# max636.net
KiCad netlist of a schematic drawn in EAGLE
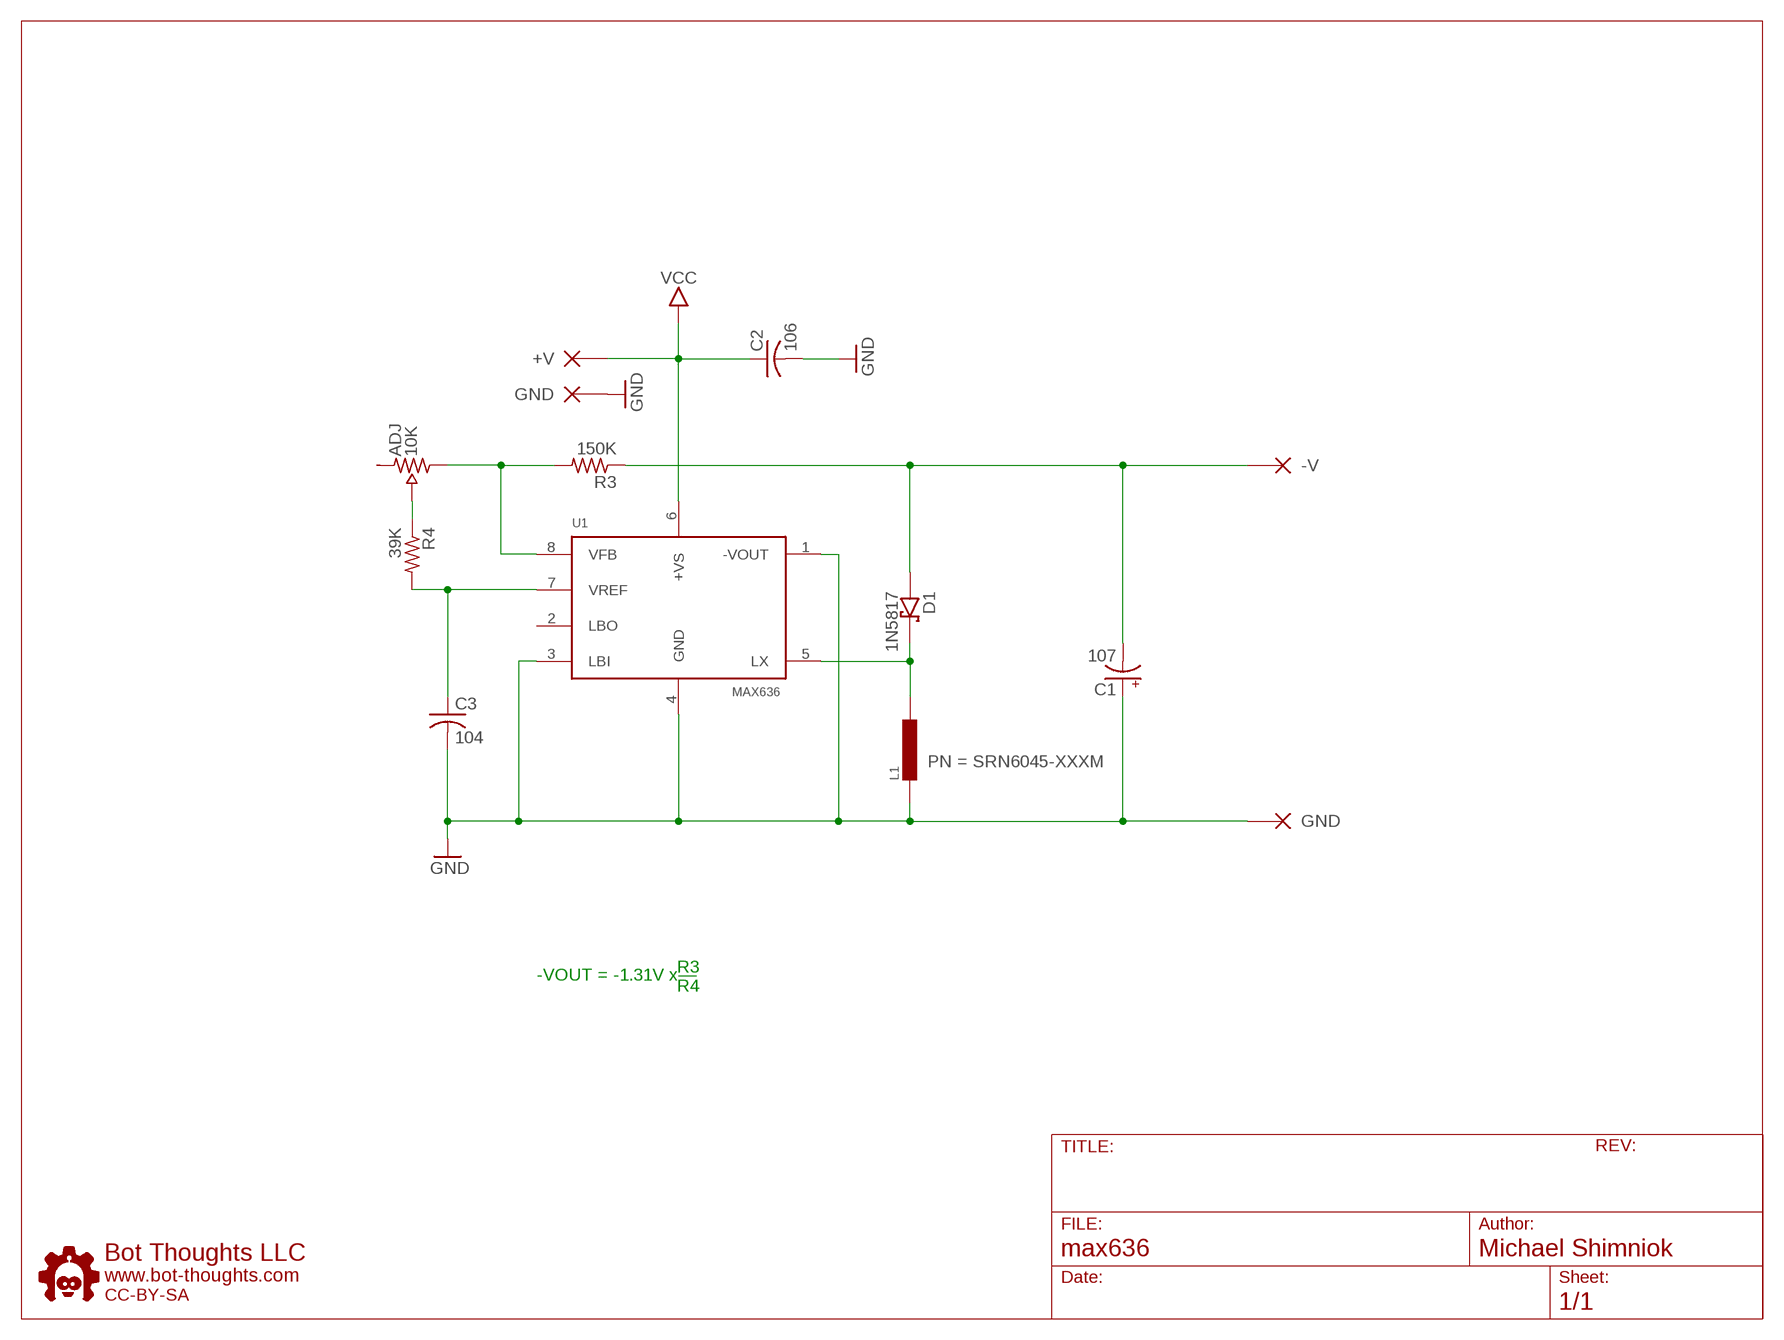
[diagram p0: schematic, sheet 1]

(export (version "E")
  (design (tool "Eeschema 10.0.6"))
  (components
    (comp (ref "ADJ")
      (value "10K")
      (footprint "eagle-import:35WR")
      (libsource (lib "eagle-import") (part "TRIM-35WR"))
    )
    (comp (ref "C1")
      (value "107")
      (footprint "eagle-import:SMC_B")
      (libsource (lib "eagle-import") (part "CPOL_SMC_B"))
    )
    (comp (ref "C2")
      (value "106")
      (footprint "eagle-import:0603")
      (libsource (lib "eagle-import") (part "C-0603"))
    )
    (comp (ref "C3")
      (value "104")
      (footprint "eagle-import:0603")
      (libsource (lib "eagle-import") (part "C-0603"))
    )
    (comp (ref "D1")
      (value "1N5817")
      (footprint "eagle-import:SOD-323")
      (libsource (lib "eagle-import") (part "SCHOTTKY-DIODE-B5817WS-TP"))
    )
    (comp (ref "J1")
      (value "+V")
      (footprint "eagle-import:1X01-S")
      (libsource (lib "eagle-import") (part "PINHEAD-1"))
    )
    (comp (ref "J2")
      (value "-V")
      (footprint "eagle-import:1X01-S")
      (libsource (lib "eagle-import") (part "PINHEAD-1"))
    )
    (comp (ref "J3")
      (value "GND")
      (footprint "eagle-import:1X01-S")
      (libsource (lib "eagle-import") (part "PINHEAD-1"))
    )
    (comp (ref "J4")
      (value "GND")
      (footprint "eagle-import:1X01-S")
      (libsource (lib "eagle-import") (part "PINHEAD-1"))
    )
    (comp (ref "L1")
      (value "INDUCTOR-VLS6045EX")
      (footprint "eagle-import:VLS6045EX")
      (fields (field (name "PN") "SRN6045-XXXM"))
      (libsource (lib "eagle-import") (part "INDUCTOR-VLS6045EX"))
    )
    (comp (ref "R3")
      (value "150K")
      (footprint "eagle-import:0603")
      (libsource (lib "eagle-import") (part "R0603"))
    )
    (comp (ref "R4")
      (value "39K")
      (footprint "eagle-import:0603")
      (libsource (lib "eagle-import") (part "R0603"))
    )
    (comp (ref "U$1")
      (value "BTLOGO-LOGO-SM")
      (footprint "eagle-import:BTLOGOS")
      (libsource (lib "eagle-import") (part "BTLOGO-LOGO-SM"))
    )
    (comp (ref "U1")
      (value "MAX636")
      (footprint "eagle-import:SO08")
      (libsource (lib "eagle-import") (part "MAX636SO8"))
    )
  )
  (nets
    (net (code "1") (name "GND") (class "Default")
      (node (ref "C1") (pin "+") (pinfunction "+_+") (pintype "passive"))
      (node (ref "C2") (pin "2") (pinfunction "-_2") (pintype "passive"))
      (node (ref "C3") (pin "2") (pinfunction "-_2") (pintype "passive"))
      (node (ref "J3") (pin "1") (pinfunction "P_1") (pintype "bidirectional"))
      (node (ref "J4") (pin "1") (pinfunction "P_1") (pintype "bidirectional"))
      (node (ref "L1") (pin "1") (pinfunction "1_1") (pintype "passive"))
      (node (ref "U1") (pin "1") (pinfunction "-VOUT_1") (pintype "power_in"))
      (node (ref "U1") (pin "3") (pinfunction "LBI_3") (pintype "bidirectional"))
      (node (ref "U1") (pin "4") (pinfunction "GND_4") (pintype "power_in"))
    )
    (net (code "2") (name "Net-(ADJ-A)") (class "Default")
      (node (ref "ADJ") (pin "1") (pinfunction "A_1") (pintype "passive"))
      (node (ref "R3") (pin "2") (pinfunction "2_2") (pintype "passive"))
      (node (ref "U1") (pin "8") (pinfunction "VFB_8") (pintype "bidirectional"))
    )
    (net (code "3") (name "Net-(ADJ-WIPER)") (class "Default")
      (node (ref "ADJ") (pin "2") (pinfunction "WIPER_2") (pintype "passive"))
      (node (ref "R4") (pin "1") (pinfunction "1_1") (pintype "passive"))
    )
    (net (code "4") (name "Net-(C3-+)") (class "Default")
      (node (ref "C3") (pin "1") (pinfunction "+_1") (pintype "passive"))
      (node (ref "R4") (pin "2") (pinfunction "2_2") (pintype "passive"))
      (node (ref "U1") (pin "7") (pinfunction "VREF_7") (pintype "bidirectional"))
    )
    (net (code "5") (name "Net-(J2-P)") (class "Default")
      (node (ref "C1") (pin "-") (pinfunction "-_-") (pintype "passive"))
      (node (ref "D1") (pin "A") (pinfunction "A_A") (pintype "passive"))
      (node (ref "J2") (pin "1") (pinfunction "P_1") (pintype "bidirectional"))
      (node (ref "R3") (pin "1") (pinfunction "1_1") (pintype "passive"))
    )
    (net (code "6") (name "Net-(U1-LX)") (class "Default")
      (node (ref "D1") (pin "C") (pinfunction "C_C") (pintype "passive"))
      (node (ref "L1") (pin "2") (pinfunction "2_2") (pintype "passive"))
      (node (ref "U1") (pin "5") (pinfunction "LX_5") (pintype "bidirectional"))
    )
    (net (code "7") (name "VCC") (class "Default")
      (node (ref "C2") (pin "1") (pinfunction "+_1") (pintype "passive"))
      (node (ref "J1") (pin "1") (pinfunction "P_1") (pintype "bidirectional"))
      (node (ref "U1") (pin "6") (pinfunction "+VS_6") (pintype "power_in"))
    )
    (net (code "8") (name "unconnected-(ADJ-B-Pad3)") (class "Default")
      (node (ref "ADJ") (pin "3") (pinfunction "B_3") (pintype "passive"))
    )
    (net (code "9") (name "unconnected-(U1-LBO-Pad2)") (class "Default")
      (node (ref "U1") (pin "2") (pinfunction "LBO_2") (pintype "bidirectional"))
    )
  )
)
